# kicanka_PCB.net
KiCad netlist of a schematic drawn in Altium Designer
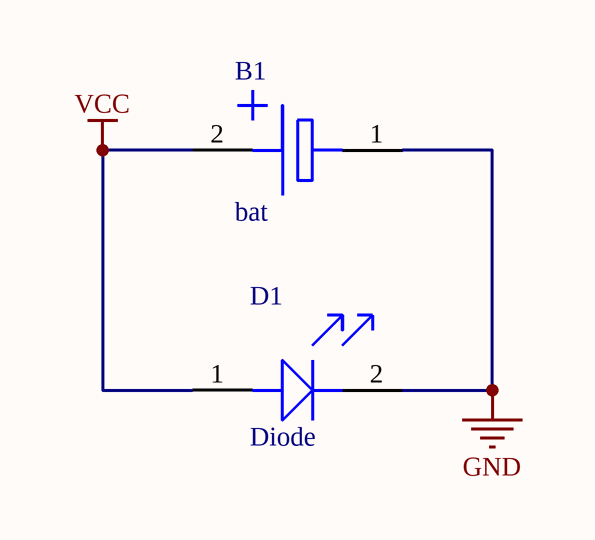
[diagram p0: kicanka_PCB.SchDoc]

(export (version "E")
  (design (tool "Eeschema 10.0.6"))
  (components
    (comp (ref "B1") (value "bat") (footprint "bat") (libsource (lib "kicanka_PCB") (part "bat")))
    (comp (ref "D1") (value "Diode") (footprint "LED") (libsource (lib "kicanka_PCB") (part "Diode")))
  )
  (nets
    (net (code "1") (name "GND") (class "Default")
      (node (ref "B1") (pin "1") (pinfunction "1_1") (pintype "open_collector"))
      (node (ref "D1") (pin "2") (pinfunction "2_2") (pintype "open_collector"))
    )
    (net (code "2") (name "VCC") (class "Default")
      (node (ref "B1") (pin "2") (pinfunction "2_2") (pintype "open_collector"))
      (node (ref "D1") (pin "1") (pinfunction "1_1") (pintype "open_collector"))
    )
  )
)
